# Smartfin_Main_PCBA_Motion.net
KiCad netlist of a schematic drawn in Altium Designer
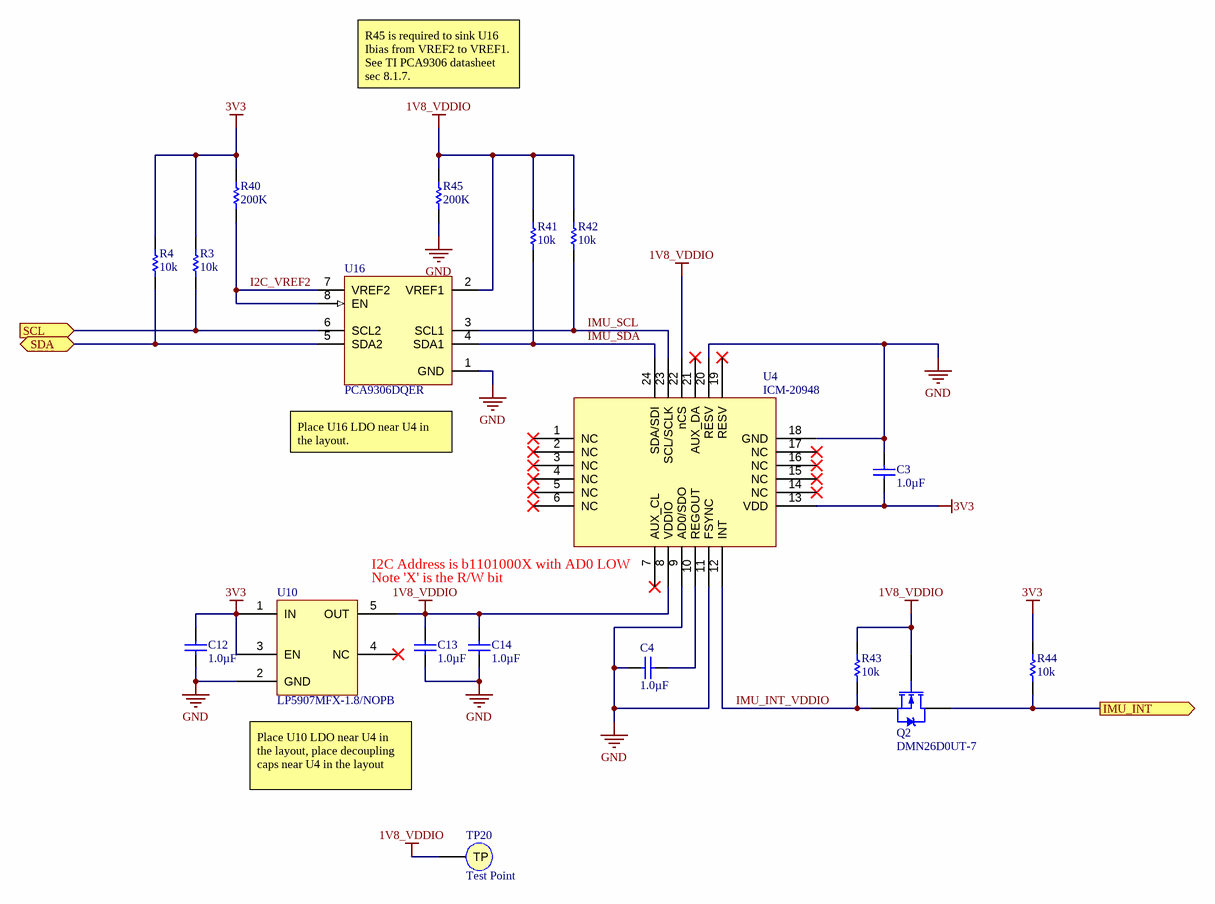
[diagram p0: Smartfin Main PCBA Motion.SchDoc]

(export (version "E")
  (design (tool "Eeschema 10.0.6"))
  (components
    (comp (ref "C3")
      (value "1.0µF")
      (footprint "CAPC0402(1005)60_N")
      (description "CAP CER 1UF 10V 10% X5R 0402")
      (fields
        (field (name "MANUFACTURER") "Yageo")
        (field (name "MANUFACTURER PART NUMBER") "CC0402KRX5R6BB105")
      )
      (libsource (lib "Syncroness Vault") (part "CAP"))
    )
    (comp (ref "C4")
      (value "1.0µF")
      (footprint "CAPC0402(1005)60_N")
      (description "CAP CER 1UF 10V 10% X5R 0402")
      (fields
        (field (name "MANUFACTURER") "Yageo")
        (field (name "MANUFACTURER PART NUMBER") "CC0402KRX5R6BB105")
      )
      (libsource (lib "Syncroness Vault") (part "CAP"))
    )
    (comp (ref "C12")
      (value "1.0µF")
      (footprint "CAPC0402(1005)60_N")
      (description "CAP CER 1UF 10V 10% X5R 0402")
      (fields
        (field (name "MANUFACTURER") "Yageo")
        (field (name "MANUFACTURER PART NUMBER") "CC0402KRX5R6BB105")
      )
      (libsource (lib "Syncroness Vault") (part "CAP"))
    )
    (comp (ref "C13")
      (value "1.0µF")
      (footprint "CAPC0402(1005)60_N")
      (description "CAP CER 1UF 10V 10% X5R 0402")
      (fields
        (field (name "MANUFACTURER") "Yageo")
        (field (name "MANUFACTURER PART NUMBER") "CC0402KRX5R6BB105")
      )
      (libsource (lib "Syncroness Vault") (part "CAP"))
    )
    (comp (ref "C14")
      (value "1.0µF")
      (footprint "CAPC0402(1005)60_N")
      (description "CAP CER 1UF 10V 10% X5R 0402")
      (fields
        (field (name "MANUFACTURER") "Yageo")
        (field (name "MANUFACTURER PART NUMBER") "CC0402KRX5R6BB105")
      )
      (libsource (lib "Syncroness Vault") (part "CAP"))
    )
    (comp (ref "Q2")
      (value "DMN26D0UT-7")
      (footprint "DMN26D0UT-7-Footprint-1")
      (description "MOSFET N-CH 20V 230MA SOT523")
      (fields (field (name "MANUFACTURER") "Diodes Incorporated"))
      (libsource (lib "Syncroness Vault") (part "DMN26D0UT-7"))
    )
    (comp (ref "R3")
      (value "10k")
      (footprint "RESC0402(1005)_N")
      (description "RES SMD 10K OHM 0.1% 1/16W 0402")
      (fields
        (field (name "TOLERANCE") "±0.1%")
        (field (name "MANUFACTURER") "Panasonic Electronic Components")
      )
      (libsource (lib "Syncroness Vault") (part "RES"))
    )
    (comp (ref "R4")
      (value "10k")
      (footprint "RESC0402(1005)_N")
      (description "RES SMD 10K OHM 0.1% 1/16W 0402")
      (fields
        (field (name "TOLERANCE") "±0.1%")
        (field (name "MANUFACTURER") "Panasonic Electronic Components")
      )
      (libsource (lib "Syncroness Vault") (part "RES"))
    )
    (comp (ref "R40")
      (value "200K")
      (footprint "RESC0402(1005)_N")
      (description "RES 200K OHM 1/16W 5% 0402 SMD")
      (fields
        (field (name "MANUFACTURER") "Yageo")
        (field (name "MANUFACTURER PART NUMBER") "RC0402JR-07200KL")
        (field (name "RESISTANCE") "200K")
      )
      (libsource (lib "Syncroness Vault") (part "RES"))
    )
    (comp (ref "R41")
      (value "10k")
      (footprint "RESC0402(1005)_N")
      (description "RES SMD 10K OHM 0.1% 1/16W 0402")
      (fields
        (field (name "TOLERANCE") "±0.1%")
        (field (name "MANUFACTURER") "Panasonic Electronic Components")
      )
      (libsource (lib "Syncroness Vault") (part "RES"))
    )
    (comp (ref "R42")
      (value "10k")
      (footprint "RESC0402(1005)_N")
      (description "RES SMD 10K OHM 0.1% 1/16W 0402")
      (fields
        (field (name "TOLERANCE") "±0.1%")
        (field (name "MANUFACTURER") "Panasonic Electronic Components")
      )
      (libsource (lib "Syncroness Vault") (part "RES"))
    )
    (comp (ref "R43")
      (value "10k")
      (footprint "RESC0402(1005)_N")
      (description "RES SMD 10K OHM 0.1% 1/16W 0402")
      (fields
        (field (name "TOLERANCE") "±0.1%")
        (field (name "MANUFACTURER") "Panasonic Electronic Components")
      )
      (libsource (lib "Syncroness Vault") (part "RES"))
    )
    (comp (ref "R44")
      (value "10k")
      (footprint "RESC0402(1005)_N")
      (description "RES SMD 10K OHM 0.1% 1/16W 0402")
      (fields
        (field (name "TOLERANCE") "±0.1%")
        (field (name "MANUFACTURER") "Panasonic Electronic Components")
      )
      (libsource (lib "Syncroness Vault") (part "RES"))
    )
    (comp (ref "R45")
      (value "200K")
      (footprint "RESC0402(1005)_N")
      (description "RES 200K OHM 1/16W 5% 0402 SMD")
      (fields
        (field (name "MANUFACTURER") "Yageo")
        (field (name "MANUFACTURER PART NUMBER") "RC0402JR-07200KL")
        (field (name "RESISTANCE") "200K")
      )
      (libsource (lib "Syncroness Vault") (part "RES"))
    )
    (comp (ref "TP20")
      (value "Test Point")
      (footprint "TESTPAD_ICT")
      (description "ICT Test Point")
      (libsource (lib "Syncroness Vault") (part "TestPointPadOnly"))
    )
    (comp (ref "U4")
      (value "ICM-20948")
      (footprint "ICM-20948-Footprint-1")
      (description "IMU ACCEL/GYRO/COMPI2C/SPI 24QFN")
      (fields (field (name "MANUFACTURER") "TDK InvenSense"))
      (libsource (lib "Syncroness Vault") (part "ICM-20948"))
    )
    (comp (ref "U10")
      (value "LP5907MFX-1.8/NOPB")
      (footprint "SOT95P280X145-5N")
      (description "IC REG LDO 1.8V 0.25A SOT23-5")
      (fields (field (name "MANUFACTURER") "Texas Instruments"))
      (libsource (lib "Syncroness Vault") (part "LP5907MFX-3.3/NOPB"))
    )
    (comp (ref "U16")
      (value "PCA9306DQER")
      (footprint "QFN35P100X140X40-8L")
      (description "IC V-LEVL XLATR I2C/SMBUS 8X2SON")
      (fields (field (name "MANUFACTURER") "Texas Instruments"))
      (libsource (lib "Syncroness Vault") (part "PCA9306DQER"))
    )
  )
  (nets
    (net (code "1") (name "/I2C_VREF2") (class "Default")
      (node (ref "R40") (pin "1") (pinfunction "1_1") (pintype "passive"))
      (node (ref "U16") (pin "7") (pinfunction "VREF2_7") (pintype "power_in"))
      (node (ref "U16") (pin "8") (pinfunction "EN_8") (pintype "input"))
    )
    (net (code "2") (name "/IMU_INT") (class "Default")
      (node (ref "Q2") (pin "D") (pinfunction "D_D") (pintype "passive"))
      (node (ref "R44") (pin "1") (pinfunction "1_1") (pintype "passive"))
    )
    (net (code "3") (name "/IMU_INT_VDDIO") (class "Default")
      (node (ref "Q2") (pin "S") (pinfunction "S_S") (pintype "passive"))
      (node (ref "R43") (pin "1") (pinfunction "1_1") (pintype "passive"))
      (node (ref "U4") (pin "12") (pinfunction "INT_12") (pintype "passive"))
    )
    (net (code "4") (name "/IMU_SCL") (class "Default")
      (node (ref "R42") (pin "1") (pinfunction "1_1") (pintype "passive"))
      (node (ref "U16") (pin "3") (pinfunction "SCL1_3") (pintype "passive"))
      (node (ref "U4") (pin "23") (pinfunction "SCL/SCLK_23") (pintype "passive"))
    )
    (net (code "5") (name "/IMU_SDA") (class "Default")
      (node (ref "R41") (pin "1") (pinfunction "1_1") (pintype "passive"))
      (node (ref "U16") (pin "4") (pinfunction "SDA1_4") (pintype "passive"))
      (node (ref "U4") (pin "24") (pinfunction "SDA/SDI_24") (pintype "passive"))
    )
    (net (code "6") (name "/SCL") (class "Default")
      (node (ref "R3") (pin "1") (pinfunction "1_1") (pintype "passive"))
      (node (ref "U16") (pin "6") (pinfunction "SCL2_6") (pintype "passive"))
    )
    (net (code "7") (name "/SDA") (class "Default")
      (node (ref "R4") (pin "1") (pinfunction "1_1") (pintype "passive"))
      (node (ref "U16") (pin "5") (pinfunction "SDA2_5") (pintype "passive"))
    )
    (net (code "8") (name "1V8_VDDIO") (class "Default")
      (node (ref "C13") (pin "2") (pinfunction "2_2") (pintype "passive"))
      (node (ref "C14") (pin "2") (pinfunction "2_2") (pintype "passive"))
      (node (ref "Q2") (pin "G") (pinfunction "G_G") (pintype "passive"))
      (node (ref "R41") (pin "2") (pinfunction "2_2") (pintype "passive"))
      (node (ref "R42") (pin "2") (pinfunction "2_2") (pintype "passive"))
      (node (ref "R43") (pin "2") (pinfunction "2_2") (pintype "passive"))
      (node (ref "R45") (pin "2") (pinfunction "2_2") (pintype "passive"))
      (node (ref "TP20") (pin "1") (pinfunction "TP_1") (pintype "passive"))
      (node (ref "U10") (pin "5") (pinfunction "OUT_5") (pintype "passive"))
      (node (ref "U16") (pin "2") (pinfunction "VREF1_2") (pintype "power_in"))
      (node (ref "U4") (pin "22") (pinfunction "nCS_22") (pintype "passive"))
      (node (ref "U4") (pin "8") (pinfunction "VDDIO_8") (pintype "passive"))
    )
    (net (code "9") (name "3V3") (class "Default")
      (node (ref "C12") (pin "2") (pinfunction "2_2") (pintype "passive"))
      (node (ref "C3") (pin "1") (pinfunction "1_1") (pintype "passive"))
      (node (ref "R3") (pin "2") (pinfunction "2_2") (pintype "passive"))
      (node (ref "R4") (pin "2") (pinfunction "2_2") (pintype "passive"))
      (node (ref "R40") (pin "2") (pinfunction "2_2") (pintype "passive"))
      (node (ref "R44") (pin "2") (pinfunction "2_2") (pintype "passive"))
      (node (ref "U10") (pin "1") (pinfunction "IN_1") (pintype "passive"))
      (node (ref "U10") (pin "3") (pinfunction "EN_3") (pintype "passive"))
      (node (ref "U4") (pin "13") (pinfunction "VDD_13") (pintype "passive"))
    )
    (net (code "10") (name "GND") (class "Default")
      (node (ref "C12") (pin "1") (pinfunction "1_1") (pintype "passive"))
      (node (ref "C13") (pin "1") (pinfunction "1_1") (pintype "passive"))
      (node (ref "C14") (pin "1") (pinfunction "1_1") (pintype "passive"))
      (node (ref "C3") (pin "2") (pinfunction "2_2") (pintype "passive"))
      (node (ref "C4") (pin "1") (pinfunction "1_1") (pintype "passive"))
      (node (ref "R45") (pin "1") (pinfunction "1_1") (pintype "passive"))
      (node (ref "U10") (pin "2") (pinfunction "GND_2") (pintype "passive"))
      (node (ref "U16") (pin "1") (pinfunction "GND_1") (pintype "power_in"))
      (node (ref "U4") (pin "11") (pinfunction "FSYNC_11") (pintype "passive"))
      (node (ref "U4") (pin "18") (pinfunction "GND_18") (pintype "passive"))
      (node (ref "U4") (pin "20") (pinfunction "RESV_20") (pintype "passive"))
      (node (ref "U4") (pin "9") (pinfunction "AD0/SDO_9") (pintype "passive"))
    )
    (net (code "11") (name "Net-(U4-REGOUT)") (class "Default")
      (node (ref "C4") (pin "2") (pinfunction "2_2") (pintype "passive"))
      (node (ref "U4") (pin "10") (pinfunction "REGOUT_10") (pintype "passive"))
    )
    (net (code "12") (name "unconnected-(U4-AUX_CL-Pad7)") (class "Default")
      (node (ref "U4") (pin "7") (pinfunction "AUX_CL_7") (pintype "passive+no_connect"))
    )
    (net (code "13") (name "unconnected-(U4-AUX_DA-Pad21)") (class "Default")
      (node (ref "U4") (pin "21") (pinfunction "AUX_DA_21") (pintype "passive+no_connect"))
    )
    (net (code "14") (name "unconnected-(U4-NC-Pad1)") (class "Default")
      (node (ref "U4") (pin "1") (pinfunction "NC_1") (pintype "passive+no_connect"))
    )
    (net (code "15") (name "unconnected-(U4-NC-Pad2)") (class "Default")
      (node (ref "U4") (pin "2") (pinfunction "NC_2") (pintype "passive+no_connect"))
    )
    (net (code "16") (name "unconnected-(U4-NC-Pad3)") (class "Default")
      (node (ref "U4") (pin "3") (pinfunction "NC_3") (pintype "passive+no_connect"))
    )
    (net (code "17") (name "unconnected-(U4-NC-Pad4)") (class "Default")
      (node (ref "U4") (pin "4") (pinfunction "NC_4") (pintype "passive+no_connect"))
    )
    (net (code "18") (name "unconnected-(U4-NC-Pad5)") (class "Default")
      (node (ref "U4") (pin "5") (pinfunction "NC_5") (pintype "passive+no_connect"))
    )
    (net (code "19") (name "unconnected-(U4-NC-Pad6)") (class "Default")
      (node (ref "U4") (pin "6") (pinfunction "NC_6") (pintype "passive+no_connect"))
    )
    (net (code "20") (name "unconnected-(U4-NC-Pad14)") (class "Default")
      (node (ref "U4") (pin "14") (pinfunction "NC_14") (pintype "passive+no_connect"))
    )
    (net (code "21") (name "unconnected-(U4-NC-Pad15)") (class "Default")
      (node (ref "U4") (pin "15") (pinfunction "NC_15") (pintype "passive+no_connect"))
    )
    (net (code "22") (name "unconnected-(U4-NC-Pad16)") (class "Default")
      (node (ref "U4") (pin "16") (pinfunction "NC_16") (pintype "passive+no_connect"))
    )
    (net (code "23") (name "unconnected-(U4-NC-Pad17)") (class "Default")
      (node (ref "U4") (pin "17") (pinfunction "NC_17") (pintype "passive+no_connect"))
    )
    (net (code "24") (name "unconnected-(U4-RESV-Pad19)") (class "Default")
      (node (ref "U4") (pin "19") (pinfunction "RESV_19") (pintype "passive+no_connect"))
    )
    (net (code "25") (name "unconnected-(U10-NC-Pad4)") (class "Default")
      (node (ref "U10") (pin "4") (pinfunction "NC_4") (pintype "passive+no_connect"))
    )
  )
)
